# 010_Fan.net
KiCad netlist of a schematic drawn in Altium Designer
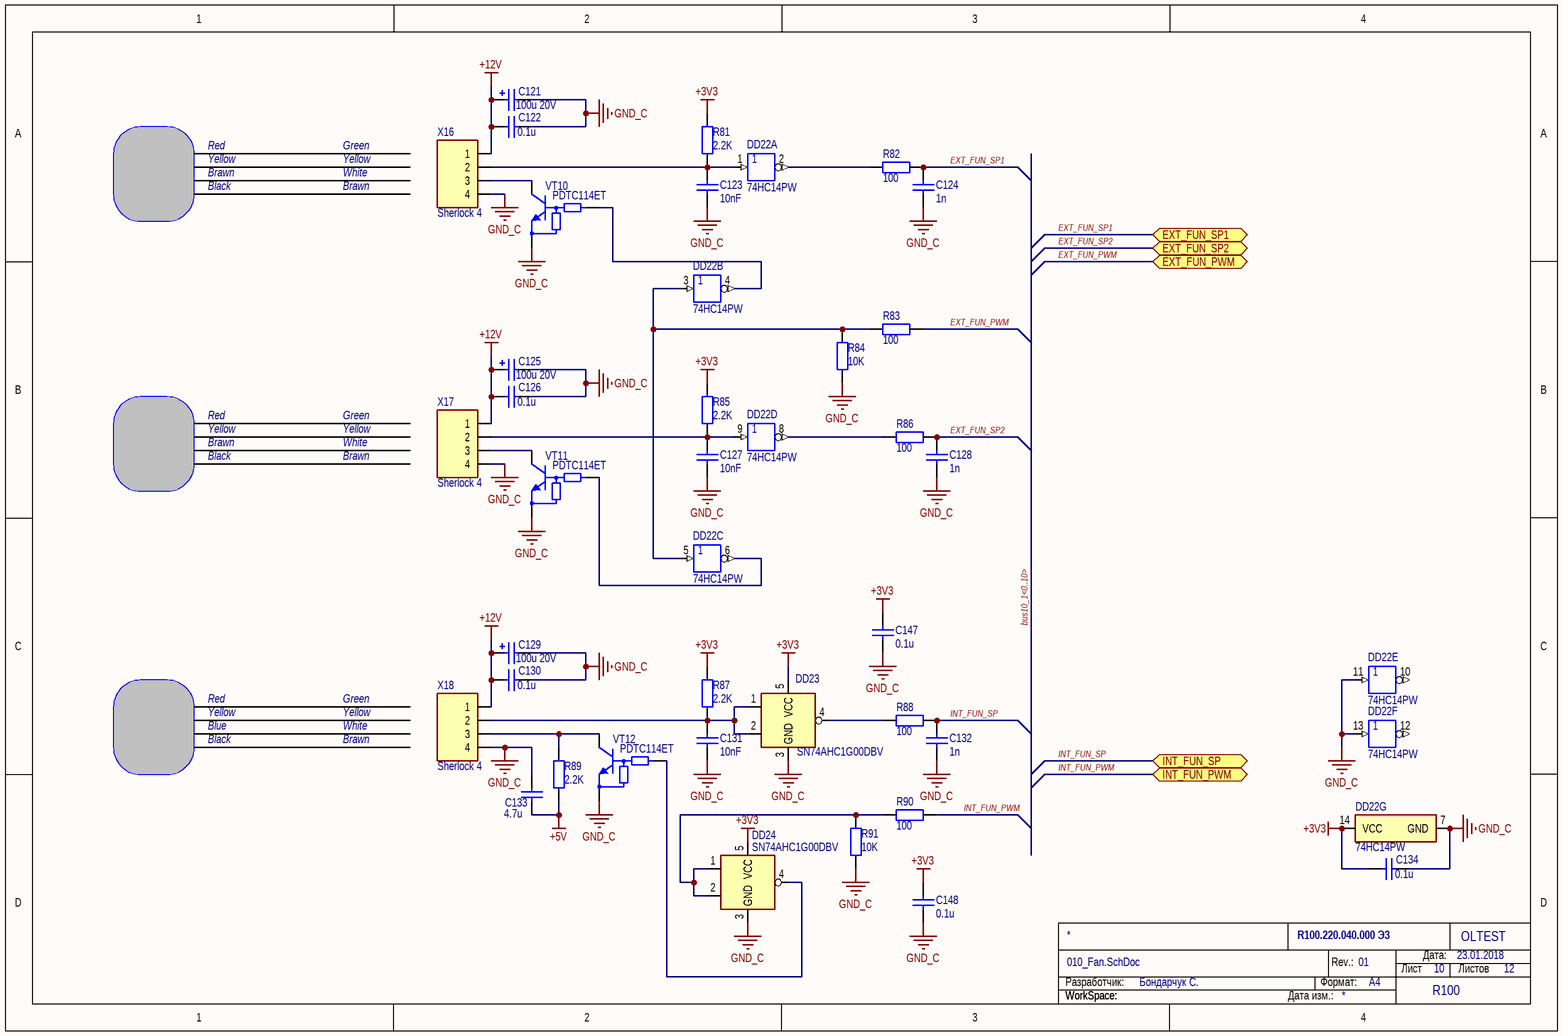
[diagram p0: 010_Fan.SchDoc]

(export (version "E")
  (design (tool "Eeschema 10.0.6"))
  (components
    (comp (ref "C121")
      (value "100u 20V")
      (footprint "mainLib:TAJD")
      (description "SMD SIZE D TANTALUM AVX 20V 10%")
      (fields (field (name "PARTNUMBER") "TAJD107K020RNJ") (field (name "MANUFACTURER") "AVX"))
      (libsource (lib "mainRCLib") (part "TECAP 100u 20V 10%"))
    )
    (comp (ref "C122")
      (value "0.1u")
      (footprint "mainLib:SMD_C_0603")
      (description "SMD C 0603 MURATA 50V 10% X7R")
      (fields (field (name "PARTNUMBER") "GRM188R71H104K") (field (name "MANUFACTURER") "MURATA"))
      (libsource (lib "mainRCLib") (part "C0603 0.1u 50V 10%"))
    )
    (comp (ref "C123")
      (value "10nF")
      (footprint "mainLib:SMD_C_0603")
      (description "SMD C 0603 MURATA 100V 10% X7R")
      (fields (field (name "PARTNUMBER") "GRJ188R72A103KE11#") (field (name "MANUFACTURER") "MURATA"))
      (libsource (lib "mainRCLib") (part "C0603 10nF 100V 10%"))
    )
    (comp (ref "C124")
      (value "1n")
      (footprint "mainLib:SMD_C_0603")
      (description "SMD C 0603 MURATA 50V 5% NP0")
      (fields (field (name "PARTNUMBER") "GRM1885C1H102JA01") (field (name "MANUFACTURER") "MURATA"))
      (libsource (lib "mainRCLib") (part "C0603 1n 50V 5%"))
    )
    (comp (ref "C125")
      (value "100u 20V")
      (footprint "mainLib:TAJD")
      (description "SMD SIZE D TANTALUM AVX 20V 10%")
      (fields (field (name "PARTNUMBER") "TAJD107K020RNJ") (field (name "MANUFACTURER") "AVX"))
      (libsource (lib "mainRCLib") (part "TECAP 100u 20V 10%"))
    )
    (comp (ref "C126")
      (value "0.1u")
      (footprint "mainLib:SMD_C_0603")
      (description "SMD C 0603 MURATA 50V 10% X7R")
      (fields (field (name "PARTNUMBER") "GRM188R71H104K") (field (name "MANUFACTURER") "MURATA"))
      (libsource (lib "mainRCLib") (part "C0603 0.1u 50V 10%"))
    )
    (comp (ref "C127")
      (value "10nF")
      (footprint "mainLib:SMD_C_0603")
      (description "SMD C 0603 MURATA 100V 10% X7R")
      (fields (field (name "PARTNUMBER") "GRJ188R72A103KE11#") (field (name "MANUFACTURER") "MURATA"))
      (libsource (lib "mainRCLib") (part "C0603 10nF 100V 10%"))
    )
    (comp (ref "C128")
      (value "1n")
      (footprint "mainLib:SMD_C_0603")
      (description "SMD C 0603 MURATA 50V 5% NP0")
      (fields (field (name "PARTNUMBER") "GRM1885C1H102JA01") (field (name "MANUFACTURER") "MURATA"))
      (libsource (lib "mainRCLib") (part "C0603 1n 50V 5%"))
    )
    (comp (ref "C129")
      (value "100u 20V")
      (footprint "mainLib:TAJD")
      (description "SMD SIZE D TANTALUM AVX 20V 10%")
      (fields (field (name "PARTNUMBER") "TAJD107K020RNJ") (field (name "MANUFACTURER") "AVX"))
      (libsource (lib "mainRCLib") (part "TECAP 100u 20V 10%"))
    )
    (comp (ref "C130")
      (value "0.1u")
      (footprint "mainLib:SMD_C_0603")
      (description "SMD C 0603 MURATA 50V 10% X7R")
      (fields (field (name "PARTNUMBER") "GRM188R71H104K") (field (name "MANUFACTURER") "MURATA"))
      (libsource (lib "mainRCLib") (part "C0603 0.1u 50V 10%"))
    )
    (comp (ref "C131")
      (value "10nF")
      (footprint "mainLib:SMD_C_0603")
      (description "SMD C 0603 MURATA 100V 10% X7R")
      (fields (field (name "PARTNUMBER") "GRJ188R72A103KE11#") (field (name "MANUFACTURER") "MURATA"))
      (libsource (lib "mainRCLib") (part "C0603 10nF 100V 10%"))
    )
    (comp (ref "C132")
      (value "1n")
      (footprint "mainLib:SMD_C_0603")
      (description "SMD C 0603 MURATA 50V 5% NP0")
      (fields (field (name "PARTNUMBER") "GRM1885C1H102JA01") (field (name "MANUFACTURER") "MURATA"))
      (libsource (lib "mainRCLib") (part "C0603 1n 50V 5%"))
    )
    (comp (ref "C133")
      (value "4.7u")
      (footprint "mainLib:SMD_C_0805")
      (description "SMD C 0805 MURATA 50V 5% NP0")
      (fields (field (name "PARTNUMBER") "GRM21BR61E475M") (field (name "MANUFACTURER") "MURATA"))
      (libsource (lib "mainRCLib") (part "C0805 4.7u 25V 20%  X5R"))
    )
    (comp (ref "C134")
      (value "0.1u")
      (footprint "mainLib:SMD_C_0603")
      (description "SMD C 0603 MURATA 50V 10% X7R")
      (fields (field (name "PARTNUMBER") "GRM188R71H104K") (field (name "MANUFACTURER") "MURATA"))
      (libsource (lib "mainRCLib") (part "C0603 0.1u 50V 10%"))
    )
    (comp (ref "C147")
      (value "0.1u")
      (footprint "mainLib:SMD_C_0603")
      (description "SMD C 0603 MURATA 50V 10% X7R")
      (fields (field (name "PARTNUMBER") "GRM188R71H104K") (field (name "MANUFACTURER") "MURATA"))
      (libsource (lib "mainRCLib") (part "C0603 0.1u 50V 10%"))
    )
    (comp (ref "C148")
      (value "0.1u")
      (footprint "mainLib:SMD_C_0603")
      (description "SMD C 0603 MURATA 50V 10% X7R")
      (fields (field (name "PARTNUMBER") "GRM188R71H104K") (field (name "MANUFACTURER") "MURATA"))
      (libsource (lib "mainRCLib") (part "C0603 0.1u 50V 10%"))
    )
    (comp (ref "DD22")
      (value "74HC14PW")
      (footprint "mainLib:TSSOP14")
      (description "Quadruple 2-Input Positive-OR Gates, PW0014A")
      (fields (field (name "MANUFACTURER") "Texas Instruments"))
      (libsource (lib "mainLib") (part "74HC14"))
    )
    (comp (ref "DD23")
      (value "SN74AHC1G00DBV")
      (footprint "mainLib:SOT-23(DBV)")
      (description "2-in NAND")
      (fields (field (name "MANUFACTURER") "Texas Instruments"))
      (libsource (lib "mainLib") (part "SN74AHC1G00DBV"))
    )
    (comp (ref "DD24")
      (value "SN74AHC1G00DBV")
      (footprint "mainLib:SOT-23(DBV)")
      (description "2-in NAND")
      (fields (field (name "MANUFACTURER") "Texas Instruments"))
      (libsource (lib "mainLib") (part "SN74AHC1G00DBV"))
    )
    (comp (ref "R81")
      (value "2.2K")
      (footprint "mainLib:SMD_R_0603")
      (description "SMD R 0603 VISHAY 0.1W 75V 1% 100ppm")
      (fields (field (name "PARTNUMBER") "CRCW06032K20FK") (field (name "MANUFACTURER") "VISHAY"))
      (libsource (lib "mainRCLib") (part "R0603 2.2K 1%"))
    )
    (comp (ref "R82")
      (value "100")
      (footprint "SMD_R_0603")
      (description "SMD R 0603 VISHAY 0.1W 75V 1% 100ppm")
      (fields (field (name "PARTNUMBER") "CRCW0603100RFK") (field (name "MANUFACTURER") "VISHAY"))
      (libsource (lib "mainRCLib") (part "R0603 100 1%"))
    )
    (comp (ref "R83")
      (value "100")
      (footprint "SMD_R_0603")
      (description "SMD R 0603 VISHAY 0.1W 75V 1% 100ppm")
      (fields (field (name "PARTNUMBER") "CRCW0603100RFK") (field (name "MANUFACTURER") "VISHAY"))
      (libsource (lib "mainRCLib") (part "R0603 100 1%"))
    )
    (comp (ref "R84")
      (value "10K")
      (footprint "SMD_R_0603")
      (description "SMD R 0603 VISHAY 0.1W 75V 1% 100ppm")
      (fields (field (name "PARTNUMBER") "CRCW060310K0FK") (field (name "MANUFACTURER") "VISHAY"))
      (libsource (lib "mainRCLib") (part "R0603 10К 1%"))
    )
    (comp (ref "R85")
      (value "2.2K")
      (footprint "mainLib:SMD_R_0603")
      (description "SMD R 0603 VISHAY 0.1W 75V 1% 100ppm")
      (fields (field (name "PARTNUMBER") "CRCW06032K20FK") (field (name "MANUFACTURER") "VISHAY"))
      (libsource (lib "mainRCLib") (part "R0603 2.2K 1%"))
    )
    (comp (ref "R86")
      (value "100")
      (footprint "SMD_R_0603")
      (description "SMD R 0603 VISHAY 0.1W 75V 1% 100ppm")
      (fields (field (name "PARTNUMBER") "CRCW0603100RFK") (field (name "MANUFACTURER") "VISHAY"))
      (libsource (lib "mainRCLib") (part "R0603 100 1%"))
    )
    (comp (ref "R87")
      (value "2.2K")
      (footprint "mainLib:SMD_R_0603")
      (description "SMD R 0603 VISHAY 0.1W 75V 1% 100ppm")
      (fields (field (name "PARTNUMBER") "CRCW06032K20FK") (field (name "MANUFACTURER") "VISHAY"))
      (libsource (lib "mainRCLib") (part "R0603 2.2K 1%"))
    )
    (comp (ref "R88")
      (value "100")
      (footprint "SMD_R_0603")
      (description "SMD R 0603 VISHAY 0.1W 75V 1% 100ppm")
      (fields (field (name "PARTNUMBER") "CRCW0603100RFK") (field (name "MANUFACTURER") "VISHAY"))
      (libsource (lib "mainRCLib") (part "R0603 100 1%"))
    )
    (comp (ref "R89")
      (value "2.2K")
      (footprint "mainLib:SMD_R_0603")
      (description "SMD R 0603 VISHAY 0.1W 75V 1% 100ppm")
      (fields (field (name "PARTNUMBER") "CRCW06032K20FK") (field (name "MANUFACTURER") "VISHAY"))
      (libsource (lib "mainRCLib") (part "R0603 2.2K 1%"))
    )
    (comp (ref "R90")
      (value "100")
      (footprint "SMD_R_0603")
      (description "SMD R 0603 VISHAY 0.1W 75V 1% 100ppm")
      (fields (field (name "PARTNUMBER") "CRCW0603100RFK") (field (name "MANUFACTURER") "VISHAY"))
      (libsource (lib "mainRCLib") (part "R0603 100 1%"))
    )
    (comp (ref "R91")
      (value "10K")
      (footprint "SMD_R_0603")
      (description "SMD R 0603 VISHAY 0.1W 75V 1% 100ppm")
      (fields (field (name "PARTNUMBER") "CRCW060310K0FK") (field (name "MANUFACTURER") "VISHAY"))
      (libsource (lib "mainRCLib") (part "R0603 10К 1%"))
    )
    (comp (ref "VT10")
      (value "PDTC114ET")
      (footprint "mainLib:SOT23-3")
      (description "Digital Transistor (BRT), R1=10 kOhm, R2=10 kOhm, NPN Transistor")
      (fields (field (name "MANUFACTURER") "On Semiconductor"))
      (libsource (lib "mainLib") (part "PDTC114ET"))
    )
    (comp (ref "VT11")
      (value "PDTC114ET")
      (footprint "mainLib:SOT23-3")
      (description "Digital Transistor (BRT), R1=10 kOhm, R2=10 kOhm, NPN Transistor")
      (fields (field (name "MANUFACTURER") "On Semiconductor"))
      (libsource (lib "mainLib") (part "PDTC114ET"))
    )
    (comp (ref "VT12")
      (value "PDTC114ET")
      (footprint "mainLib:SOT23-3")
      (description "Digital Transistor (BRT), R1=10 kOhm, R2=10 kOhm, NPN Transistor")
      (fields (field (name "MANUFACTURER") "On Semiconductor"))
      (libsource (lib "mainLib") (part "PDTC114ET"))
    )
    (comp (ref "X16")
      (value "Sherlock 4")
      (footprint "35362-0450")
      (description "Sherlock 4 Top, 2A 125V 2mm")
      (fields (field (name "PARTNUMBER") "35362-0450") (field (name "MANUFACTURER") "MOLEX"))
      (libsource (lib "mainLib") (part "35362-0450"))
    )
    (comp (ref "X17")
      (value "Sherlock 4")
      (footprint "35362-0450")
      (description "Sherlock 4 Top, 2A 125V 2mm")
      (fields (field (name "PARTNUMBER") "35362-0450") (field (name "MANUFACTURER") "MOLEX"))
      (libsource (lib "mainLib") (part "35362-0450"))
    )
    (comp (ref "X18")
      (value "Sherlock 4")
      (footprint "35362-0450")
      (description "Sherlock 4 Top, 2A 125V 2mm")
      (fields (field (name "PARTNUMBER") "35362-0450") (field (name "MANUFACTURER") "MOLEX"))
      (libsource (lib "mainLib") (part "35362-0450"))
    )
  )
  (nets
    (net (code "2") (name "+3V3") (class "Default")
      (node (ref "C134") (pin "1") (pinfunction "1_1") (pintype "passive"))
      (node (ref "C147") (pin "2") (pinfunction "2_2") (pintype "passive"))
      (node (ref "C148") (pin "2") (pinfunction "2_2") (pintype "passive"))
      (node (ref "DD22") (pin "14") (pinfunction "VCC_14") (pintype "power_in"))
      (node (ref "DD23") (pin "5") (pinfunction "VCC_5") (pintype "passive"))
      (node (ref "DD24") (pin "5") (pinfunction "VCC_5") (pintype "passive"))
      (node (ref "R81") (pin "2") (pinfunction "2_2") (pintype "passive"))
      (node (ref "R85") (pin "2") (pinfunction "2_2") (pintype "passive"))
      (node (ref "R87") (pin "2") (pinfunction "2_2") (pintype "passive"))
    )
    (net (code "3") (name "+5V") (class "Default")
      (node (ref "C133") (pin "1") (pinfunction "1_1") (pintype "passive"))
      (node (ref "R89") (pin "1") (pinfunction "1_1") (pintype "passive"))
    )
    (net (code "4") (name "+12V") (class "Default")
      (node (ref "C121") (pin "1") (pinfunction "1_1") (pintype "passive"))
      (node (ref "C122") (pin "1") (pinfunction "1_1") (pintype "passive"))
      (node (ref "C125") (pin "1") (pinfunction "1_1") (pintype "passive"))
      (node (ref "C126") (pin "1") (pinfunction "1_1") (pintype "passive"))
      (node (ref "C129") (pin "1") (pinfunction "1_1") (pintype "passive"))
      (node (ref "C130") (pin "1") (pinfunction "1_1") (pintype "passive"))
      (node (ref "X16") (pin "1") (pinfunction "1_1") (pintype "passive"))
      (node (ref "X17") (pin "1") (pinfunction "1_1") (pintype "passive"))
      (node (ref "X18") (pin "1") (pinfunction "1_1") (pintype "passive"))
    )
    (net (code "5") (name "/EXT_FUN_PWM") (class "Default")
      (node (ref "R83") (pin "2") (pinfunction "2_2") (pintype "passive"))
    )
    (net (code "6") (name "/EXT_FUN_SP1") (class "Default")
      (node (ref "C124") (pin "2") (pinfunction "2_2") (pintype "passive"))
      (node (ref "R82") (pin "2") (pinfunction "2_2") (pintype "passive"))
    )
    (net (code "7") (name "/EXT_FUN_SP2") (class "Default")
      (node (ref "C128") (pin "2") (pinfunction "2_2") (pintype "passive"))
      (node (ref "R86") (pin "2") (pinfunction "2_2") (pintype "passive"))
    )
    (net (code "8") (name "/INT_FUN_PWM") (class "Default")
      (node (ref "R90") (pin "2") (pinfunction "2_2") (pintype "passive"))
    )
    (net (code "9") (name "/INT_FUN_SP") (class "Default")
      (node (ref "C132") (pin "2") (pinfunction "2_2") (pintype "passive"))
      (node (ref "R88") (pin "2") (pinfunction "2_2") (pintype "passive"))
    )
    (net (code "11") (name "GND_C") (class "Default")
      (node (ref "C121") (pin "2") (pinfunction "2_2") (pintype "passive"))
      (node (ref "C122") (pin "2") (pinfunction "2_2") (pintype "passive"))
      (node (ref "C123") (pin "2") (pinfunction "2_2") (pintype "passive"))
      (node (ref "C124") (pin "1") (pinfunction "1_1") (pintype "passive"))
      (node (ref "C125") (pin "2") (pinfunction "2_2") (pintype "passive"))
      (node (ref "C126") (pin "2") (pinfunction "2_2") (pintype "passive"))
      (node (ref "C127") (pin "2") (pinfunction "2_2") (pintype "passive"))
      (node (ref "C128") (pin "1") (pinfunction "1_1") (pintype "passive"))
      (node (ref "C129") (pin "2") (pinfunction "2_2") (pintype "passive"))
      (node (ref "C130") (pin "2") (pinfunction "2_2") (pintype "passive"))
      (node (ref "C131") (pin "2") (pinfunction "2_2") (pintype "passive"))
      (node (ref "C132") (pin "1") (pinfunction "1_1") (pintype "passive"))
      (node (ref "C133") (pin "2") (pinfunction "2_2") (pintype "passive"))
      (node (ref "C134") (pin "2") (pinfunction "2_2") (pintype "passive"))
      (node (ref "C147") (pin "1") (pinfunction "1_1") (pintype "passive"))
      (node (ref "C148") (pin "1") (pinfunction "1_1") (pintype "passive"))
      (node (ref "DD22") (pin "11") (pinfunction "5A_11") (pintype "input"))
      (node (ref "DD22") (pin "13") (pinfunction "6A_13") (pintype "input"))
      (node (ref "DD22") (pin "7") (pinfunction "GND_7") (pintype "power_in"))
      (node (ref "DD23") (pin "3") (pinfunction "GND_3") (pintype "passive"))
      (node (ref "DD24") (pin "3") (pinfunction "GND_3") (pintype "passive"))
      (node (ref "R84") (pin "1") (pinfunction "1_1") (pintype "passive"))
      (node (ref "R91") (pin "1") (pinfunction "1_1") (pintype "passive"))
      (node (ref "VT10") (pin "2") (pinfunction "E_2") (pintype "passive"))
      (node (ref "VT11") (pin "2") (pinfunction "E_2") (pintype "passive"))
      (node (ref "VT12") (pin "2") (pinfunction "E_2") (pintype "passive"))
      (node (ref "X16") (pin "4") (pinfunction "4_4") (pintype "passive"))
      (node (ref "X17") (pin "4") (pinfunction "4_4") (pintype "passive"))
      (node (ref "X18") (pin "4") (pinfunction "4_4") (pintype "passive"))
    )
    (net (code "12") (name "Net-(C131-Pad1)") (class "Default")
      (node (ref "C131") (pin "1") (pinfunction "1_1") (pintype "passive"))
      (node (ref "DD23") (pin "1") (pintype "passive"))
      (node (ref "DD23") (pin "2") (pintype "passive"))
      (node (ref "R87") (pin "1") (pinfunction "1_1") (pintype "passive"))
      (node (ref "X18") (pin "2") (pinfunction "2_2") (pintype "passive"))
    )
    (net (code "13") (name "Net-(DD22A-1A)") (class "Default")
      (node (ref "C123") (pin "1") (pinfunction "1_1") (pintype "passive"))
      (node (ref "DD22") (pin "1") (pinfunction "1A_1") (pintype "input"))
      (node (ref "R81") (pin "1") (pinfunction "1_1") (pintype "passive"))
      (node (ref "X16") (pin "2") (pinfunction "2_2") (pintype "passive"))
    )
    (net (code "14") (name "Net-(DD22A-1Y)") (class "Default")
      (node (ref "DD22") (pin "2") (pinfunction "1Y_2") (pintype "output"))
      (node (ref "R82") (pin "1") (pinfunction "1_1") (pintype "passive"))
    )
    (net (code "15") (name "Net-(DD22B-2A)") (class "Default")
      (node (ref "DD22") (pin "3") (pinfunction "2A_3") (pintype "input"))
      (node (ref "DD22") (pin "5") (pinfunction "3A_5") (pintype "input"))
      (node (ref "R83") (pin "1") (pinfunction "1_1") (pintype "passive"))
      (node (ref "R84") (pin "2") (pinfunction "2_2") (pintype "passive"))
    )
    (net (code "16") (name "Net-(DD22B-2Y)") (class "Default")
      (node (ref "DD22") (pin "4") (pinfunction "2Y_4") (pintype "output"))
      (node (ref "VT10") (pin "1") (pinfunction "B_1") (pintype "passive"))
    )
    (net (code "17") (name "Net-(DD22C-3Y)") (class "Default")
      (node (ref "DD22") (pin "6") (pinfunction "3Y_6") (pintype "output"))
      (node (ref "VT11") (pin "1") (pinfunction "B_1") (pintype "passive"))
    )
    (net (code "18") (name "Net-(DD22D-4A)") (class "Default")
      (node (ref "C127") (pin "1") (pinfunction "1_1") (pintype "passive"))
      (node (ref "DD22") (pin "9") (pinfunction "4A_9") (pintype "input"))
      (node (ref "R85") (pin "1") (pinfunction "1_1") (pintype "passive"))
      (node (ref "X17") (pin "2") (pinfunction "2_2") (pintype "passive"))
    )
    (net (code "19") (name "Net-(DD22D-4Y)") (class "Default")
      (node (ref "DD22") (pin "8") (pinfunction "4Y_8") (pintype "output"))
      (node (ref "R86") (pin "1") (pinfunction "1_1") (pintype "passive"))
    )
    (net (code "20") (name "Net-(DD23-Pad4)") (class "Default")
      (node (ref "DD23") (pin "4") (pintype "passive"))
      (node (ref "R88") (pin "1") (pinfunction "1_1") (pintype "passive"))
    )
    (net (code "21") (name "Net-(DD24-Pad1)") (class "Default")
      (node (ref "DD24") (pin "1") (pintype "passive"))
      (node (ref "DD24") (pin "2") (pintype "passive"))
      (node (ref "R90") (pin "1") (pinfunction "1_1") (pintype "passive"))
      (node (ref "R91") (pin "2") (pinfunction "2_2") (pintype "passive"))
    )
    (net (code "22") (name "Net-(VT10-C)") (class "Default")
      (node (ref "VT10") (pin "3") (pinfunction "C_3") (pintype "passive"))
      (node (ref "X16") (pin "3") (pinfunction "3_3") (pintype "passive"))
    )
    (net (code "23") (name "Net-(VT11-C)") (class "Default")
      (node (ref "VT11") (pin "3") (pinfunction "C_3") (pintype "passive"))
      (node (ref "X17") (pin "3") (pinfunction "3_3") (pintype "passive"))
    )
    (net (code "24") (name "Net-(VT12-B)") (class "Default")
      (node (ref "DD24") (pin "4") (pintype "passive"))
      (node (ref "VT12") (pin "1") (pinfunction "B_1") (pintype "passive"))
    )
    (net (code "25") (name "Net-(VT12-C)") (class "Default")
      (node (ref "R89") (pin "2") (pinfunction "2_2") (pintype "passive"))
      (node (ref "VT12") (pin "3") (pinfunction "C_3") (pintype "passive"))
      (node (ref "X18") (pin "3") (pinfunction "3_3") (pintype "passive"))
    )
    (net (code "26") (name "unconnected-(DD22E-5Y-Pad10)") (class "Default")
      (node (ref "DD22") (pin "10") (pinfunction "5Y_10") (pintype "output"))
    )
    (net (code "27") (name "unconnected-(DD22F-6Y-Pad12)") (class "Default")
      (node (ref "DD22") (pin "12") (pinfunction "6Y_12") (pintype "output"))
    )
  )
)
